# ref_mcp1502_2p5.net
KiCad netlist of a schematic drawn in Altium Designer
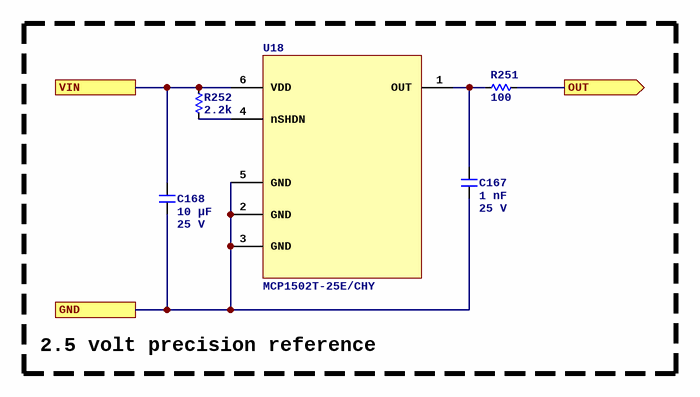
[diagram p0: ref_mcp1502_2p5.SchDoc]

(export (version "E")
  (design (tool "Eeschema 10.0.6"))
  (components
    (comp (ref "C167")
      (value "C1005C0G1E102JT000F")
      (footprint "C0402")
      (fields
        (field (name "CAPACITANCE") "1 nF")
        (field (name "MANUFACTURER") "TDK")
        (field (name "VOLTAGE RATING") "25 V")
      )
      (libsource (lib "database") (part "__template_cap"))
    )
    (comp (ref "C168")
      (value "CL10A106MA8NRNC")
      (footprint "C0603")
      (fields
        (field (name "CAPACITANCE") "10 µF")
        (field (name "MANUFACTURER") "Samsung Electro-Mechanics")
        (field (name "VOLTAGE RATING") "25 V")
      )
      (libsource (lib "database") (part "__template_cap"))
    )
    (comp (ref "R251")
      (value "100")
      (footprint "R0402")
      (fields
        (field (name "TOLERANCE") "1%")
        (field (name "MANUFACTURER PART NUMBER") "RC0402FR-07100RL")
        (field (name "MANUFACTURER") "YAGEO")
      )
      (libsource (lib "database") (part "__template_resistor"))
    )
    (comp (ref "R252")
      (value "2.2k")
      (footprint "R0402")
      (fields
        (field (name "TOLERANCE") "1%")
        (field (name "MANUFACTURER PART NUMBER") "0402WGF2201TCE")
        (field (name "MANUFACTURER") "UNI-ROYAL(Uniroyal Elec)")
      )
      (libsource (lib "database") (part "__template_resistor"))
    )
    (comp (ref "U18")
      (value "MCP1502T-25E/CHY")
      (footprint "6SOT23")
      (description "IC 7 PPM 0.1% VOLTAGE REFERENCE Series Voltage Reference IC Fixed 2.5V V ±0.1% 20 mA SOT-23-6")
      (fields (field (name "MANUFACTURER") "Microchip"))
      (libsource (lib "database") (part "MCP1502T-25E/CHY"))
    )
  )
  (nets
    (net (code "1") (name "/GND") (class "Default")
      (node (ref "C167") (pin "2") (pintype "passive"))
      (node (ref "C168") (pin "2") (pintype "passive"))
      (node (ref "U18") (pin "2") (pinfunction "GND_2") (pintype "passive"))
      (node (ref "U18") (pin "3") (pinfunction "GND_3") (pintype "passive"))
      (node (ref "U18") (pin "5") (pinfunction "GND_5") (pintype "passive"))
    )
    (net (code "2") (name "/OUT") (class "Default") (node (ref "R251") (pin "2") (pintype "passive")))
    (net (code "3") (name "/VIN") (class "Default")
      (node (ref "C168") (pin "1") (pintype "passive"))
      (node (ref "R252") (pin "1") (pintype "passive"))
      (node (ref "U18") (pin "6") (pinfunction "VDD_6") (pintype "passive"))
    )
    (net (code "4") (name "Net-(U18-OUT)") (class "Default")
      (node (ref "C167") (pin "1") (pintype "passive"))
      (node (ref "R251") (pin "1") (pintype "passive"))
      (node (ref "U18") (pin "1") (pinfunction "OUT_1") (pintype "passive"))
    )
    (net (code "5") (name "Net-(U18-nSHDN)") (class "Default")
      (node (ref "R252") (pin "2") (pintype "passive"))
      (node (ref "U18") (pin "4") (pinfunction "nSHDN_4") (pintype "passive"))
    )
  )
)
